# 105358-3SC001-03_BlockDiagram.net
KiCad netlist of a schematic drawn in Altium Designer
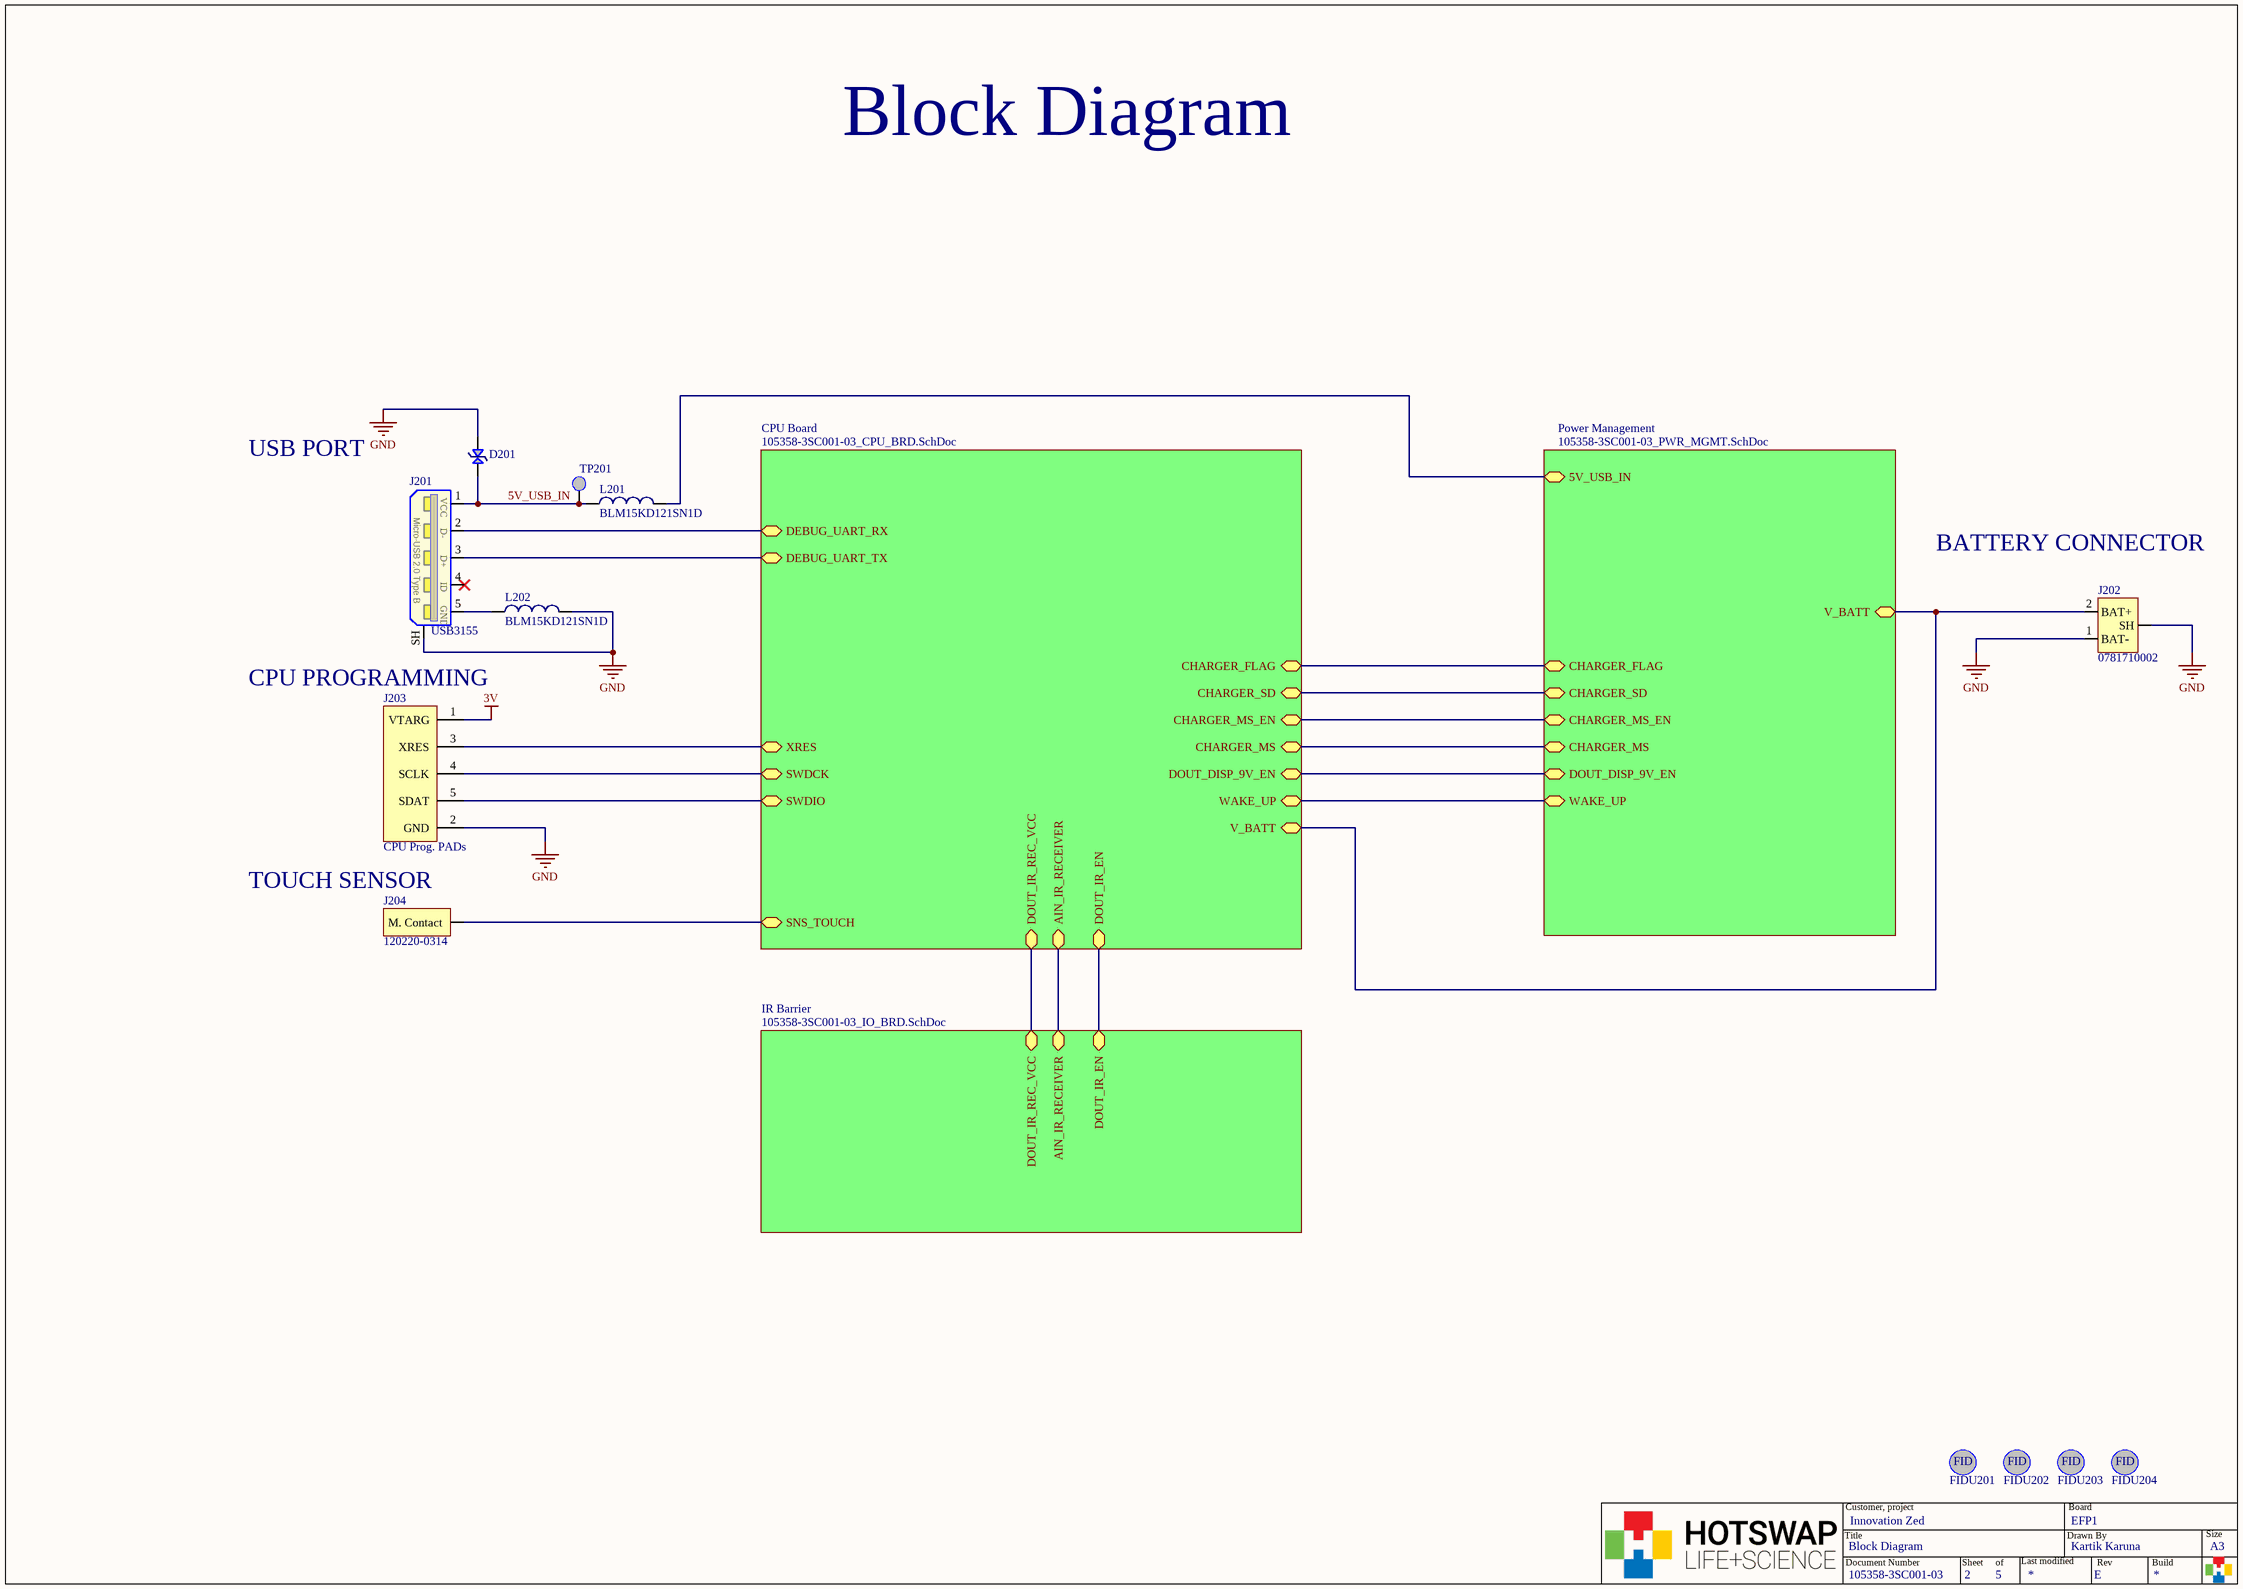
[diagram p0: 105358-3SC001-03_BlockDiagram.SchDoc]

(export (version "E")
  (design (tool "Eeschema 10.0.6"))
  (components
    (comp (ref "D201")
      (value "LXES15AAA1-133")
      (footprint "0402C-GENERIC")
      (description "TVS DIODE 15VWM 0402")
      (fields
        (field (name "MANUFACTURER") "Murata Electronics North America")
        (field (name "DIGI-KEY PART NUMBER") "490-13209-1-ND")
      )
      (libsource (lib "ConnectMedical") (part "TVS DIODE 15VWM 0402"))
    )
    (comp (ref "FIDU201")
      (value "FIDU-miniROUND")
      (footprint "FIDU-MINI-ROUND")
      (libsource (lib "ConnectMedical") (part "FIDU-miniROUND"))
    )
    (comp (ref "FIDU202")
      (value "FIDU-miniROUND")
      (footprint "FIDU-MINI-ROUND")
      (libsource (lib "ConnectMedical") (part "FIDU-miniROUND"))
    )
    (comp (ref "FIDU203")
      (value "FIDU-miniROUND")
      (footprint "FIDU-MINI-ROUND")
      (libsource (lib "ConnectMedical") (part "FIDU-miniROUND"))
    )
    (comp (ref "FIDU204")
      (value "FIDU-miniROUND")
      (footprint "FIDU-MINI-ROUND")
      (libsource (lib "ConnectMedical") (part "FIDU-miniROUND"))
    )
    (comp (ref "J201")
      (value "USB3155")
      (footprint "USB3155")
      (description "CONN RCPT USB-mini B 2.0 5POS SLD")
      (fields
        (field (name "MANUFACTURER") "GCT (GLOBAL CONNECTOR TECHNOLOGY)")
        (field (name "MANUFACTURER PART NUMBER") "USB3155-30-A")
      )
      (libsource (lib "ConnectMedical") (part "USB3155"))
    )
    (comp (ref "J202")
      (value "0781710002")
      (footprint "PAD 0781710002")
      (description "1.20MM WTB HEADER VERT 2POS")
      (fields (field (name "MANUFACTURER") "Molex, LLC") (field (name "DIGI-KEY PART NUMBER") "WM4459CT-ND"))
      (libsource (lib "ConnectMedical") (part "CONNECTOR 1.20MM WTB HEADER VERT 2POS"))
    )
    (comp (ref "J203")
      (value "CPU Prog. PADs")
      (footprint "PAD PROGRAMMING")
      (description "CPU Programming PADs")
      (libsource (lib "ConnectMedical") (part "PROGRAMMING PADS"))
    )
    (comp (ref "J204")
      (value "120220-0314")
      (footprint "PAD 1.0x1.95mm-MOD")
      (description "MICRO UNIVERSAL CONTACT Z 3.5MM")
      (fields
        (field (name "MANUFACTURER") "ITT Cannon, LLC")
        (field (name "DIGI-KEY PART NUMBER") "1003-2383-2-ND")
      )
      (libsource (lib "ConnectMedical") (part "UNIVERSAL_CONTACT_3.5MM SMD"))
    )
    (comp (ref "L201")
      (value "BLM15KD121SN1D")
      (footprint "0402L_High Speed")
      (description "FERRITE BEAD 120 OHM 0402 1LN")
      (fields
        (field (name "DIGI-KEY PART NUMBER") "490-15015-1-ND")
        (field (name "MANUFACTURER") "Murata Electronics North America")
      )
      (libsource (lib "ConnectMedical") (part "0402L_FERRITE BEAD"))
    )
    (comp (ref "L202")
      (value "BLM15KD121SN1D")
      (footprint "0402L_High Speed")
      (description "FERRITE BEAD 120 OHM 0402 1LN")
      (fields
        (field (name "DIGI-KEY PART NUMBER") "490-15015-1-ND")
        (field (name "MANUFACTURER") "Murata Electronics North America")
      )
      (libsource (lib "ConnectMedical") (part "0402L_FERRITE BEAD"))
    )
    (comp (ref "TP201")
      (value "TEST POINT")
      (footprint "PAD TEST POINT")
      (description "Testing Poiny")
      (libsource (lib "ConnectMedical") (part "TEST POINT"))
    )
  )
  (nets
    (net (code "1") (name "/5V_USB_IN") (class "Default")
      (node (ref "D201") (pin "2") (pinfunction "2_2") (pintype "passive"))
      (node (ref "J201") (pin "1") (pinfunction "VCC_1") (pintype "passive"))
      (node (ref "L201") (pin "1") (pinfunction "1_1") (pintype "passive"))
      (node (ref "TP201") (pin "1") (pinfunction "Test_Point_1") (pintype "passive"))
    )
    (net (code "2") (name "/5V_USB_IN_1") (class "Default")
      (node (ref "L201") (pin "2") (pinfunction "2_2") (pintype "passive"))
    )
    (net (code "8") (name "/DEBUG_UART_RX") (class "Default")
      (node (ref "J201") (pin "2") (pinfunction "D-_2") (pintype "passive"))
    )
    (net (code "9") (name "/DEBUG_UART_TX") (class "Default")
      (node (ref "J201") (pin "3") (pinfunction "D+_3") (pintype "passive"))
    )
    (net (code "13") (name "/SNS_TOUCH") (class "Default")
      (node (ref "J204") (pin "1") (pinfunction "M._Contact_1") (pintype "passive"))
    )
    (net (code "14") (name "/SWDCK") (class "Default")
      (node (ref "J203") (pin "4") (pinfunction "SCLK_4") (pintype "passive"))
    )
    (net (code "15") (name "/SWDIO") (class "Default")
      (node (ref "J203") (pin "5") (pinfunction "SDAT_5") (pintype "passive"))
    )
    (net (code "16") (name "/V_BATT") (class "Default")
      (node (ref "J202") (pin "2") (pinfunction "BAT+_2") (pintype "passive"))
    )
    (net (code "18") (name "/XRES") (class "Default")
      (node (ref "J203") (pin "3") (pinfunction "XRES_3") (pintype "passive"))
    )
    (net (code "19") (name "3V") (class "Default")
      (node (ref "J203") (pin "1") (pinfunction "VTARG_1") (pintype "passive"))
    )
    (net (code "20") (name "GND") (class "Default")
      (node (ref "D201") (pin "1") (pinfunction "1_1") (pintype "passive"))
      (node (ref "J201") (pin "SH") (pinfunction "Shell_SH") (pintype "passive"))
      (node (ref "J202") (pin "1") (pinfunction "BAT-_1") (pintype "passive"))
      (node (ref "J202") (pin "3") (pinfunction "SH_3") (pintype "passive"))
      (node (ref "J203") (pin "2") (pinfunction "GND_2") (pintype "passive"))
      (node (ref "L202") (pin "2") (pinfunction "2_2") (pintype "passive"))
    )
    (net (code "21") (name "Net-(J201-GND)") (class "Default")
      (node (ref "J201") (pin "5") (pinfunction "GND_5") (pintype "passive"))
      (node (ref "L202") (pin "1") (pinfunction "1_1") (pintype "passive"))
    )
    (net (code "22") (name "unconnected-(J201-ID-Pad4)") (class "Default")
      (node (ref "J201") (pin "4") (pinfunction "ID_4") (pintype "passive+no_connect"))
    )
  )
)
